# volume.net
KiCad netlist of a schematic drawn in EAGLE
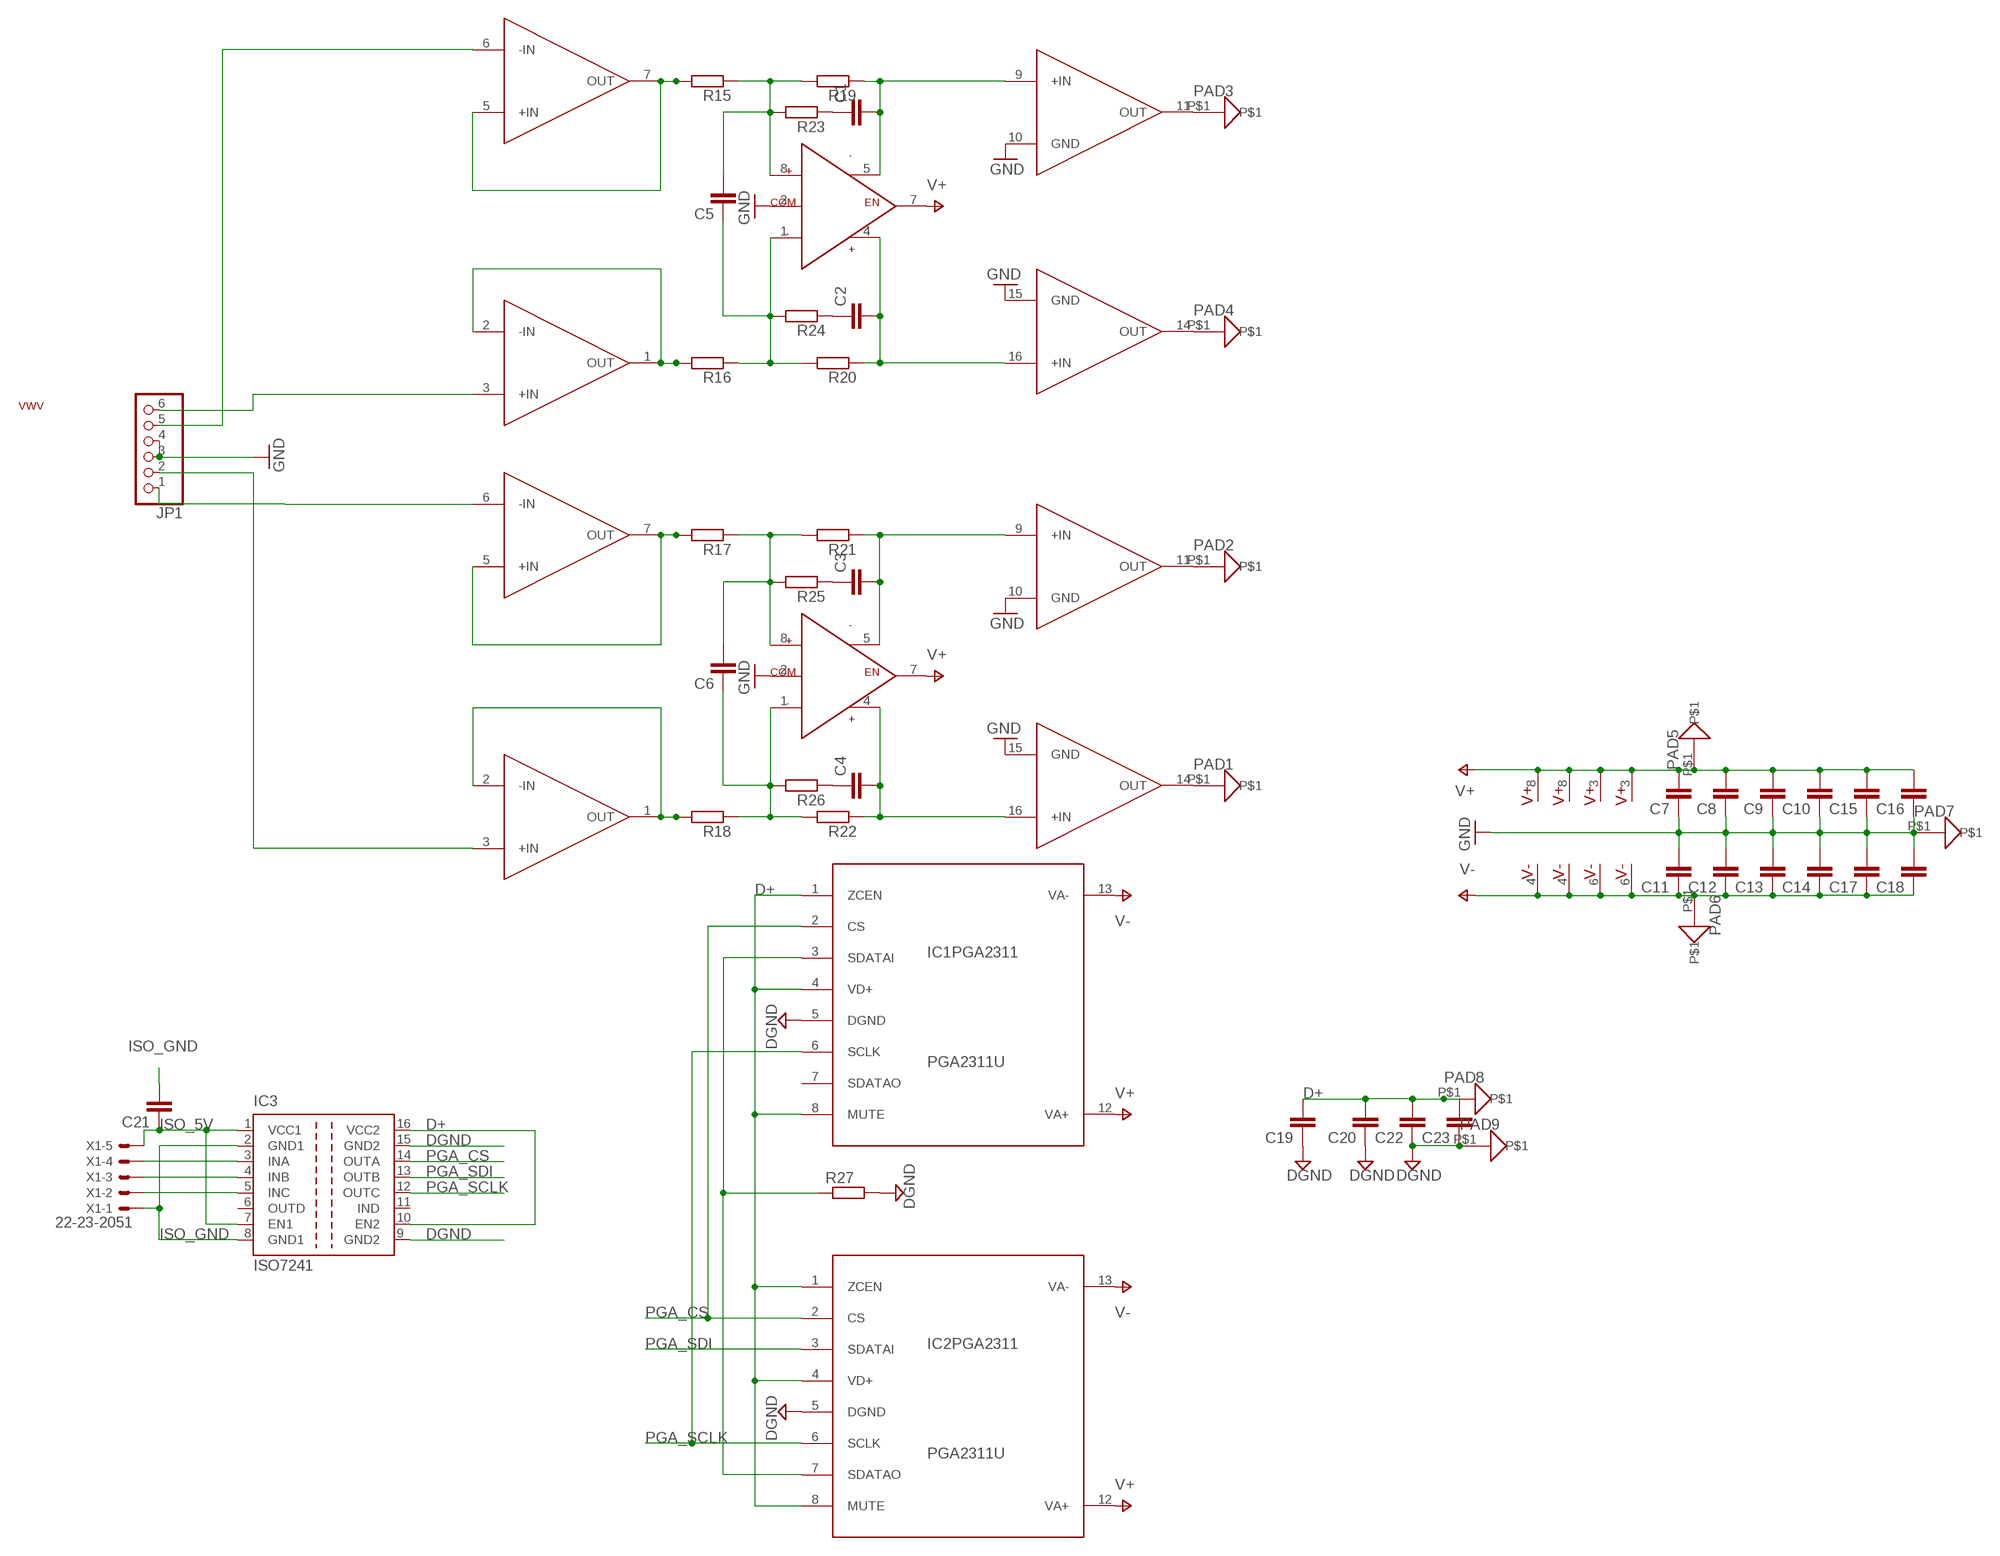
[diagram p0: schematic, sheet 1]

(export (version "E")
  (design (tool "Eeschema 10.0.6"))
  (components
    (comp (ref "C1")
      (value "C-EUC0805")
      (footprint "eagle-import:C0805")
      (libsource (lib "eagle-import") (part "C-EUC0805"))
    )
    (comp (ref "C2")
      (value "C-EUC0805")
      (footprint "eagle-import:C0805")
      (libsource (lib "eagle-import") (part "C-EUC0805"))
    )
    (comp (ref "C3")
      (value "C-EUC0805")
      (footprint "eagle-import:C0805")
      (libsource (lib "eagle-import") (part "C-EUC0805"))
    )
    (comp (ref "C4")
      (value "C-EUC0805")
      (footprint "eagle-import:C0805")
      (libsource (lib "eagle-import") (part "C-EUC0805"))
    )
    (comp (ref "C5")
      (value "C-EUC0805")
      (footprint "eagle-import:C0805")
      (libsource (lib "eagle-import") (part "C-EUC0805"))
    )
    (comp (ref "C6")
      (value "C-EUC0805")
      (footprint "eagle-import:C0805")
      (libsource (lib "eagle-import") (part "C-EUC0805"))
    )
    (comp (ref "C7")
      (value "C-EUC0805")
      (footprint "eagle-import:C0805")
      (libsource (lib "eagle-import") (part "C-EUC0805"))
    )
    (comp (ref "C8")
      (value "C-EUC0805")
      (footprint "eagle-import:C0805")
      (libsource (lib "eagle-import") (part "C-EUC0805"))
    )
    (comp (ref "C9")
      (value "C-EUC0805")
      (footprint "eagle-import:C0805")
      (libsource (lib "eagle-import") (part "C-EUC0805"))
    )
    (comp (ref "C10")
      (value "C-EUC0805")
      (footprint "eagle-import:C0805")
      (libsource (lib "eagle-import") (part "C-EUC0805"))
    )
    (comp (ref "C11")
      (value "C-EUC0805")
      (footprint "eagle-import:C0805")
      (libsource (lib "eagle-import") (part "C-EUC0805"))
    )
    (comp (ref "C12")
      (value "C-EUC0805")
      (footprint "eagle-import:C0805")
      (libsource (lib "eagle-import") (part "C-EUC0805"))
    )
    (comp (ref "C13")
      (value "C-EUC0805")
      (footprint "eagle-import:C0805")
      (libsource (lib "eagle-import") (part "C-EUC0805"))
    )
    (comp (ref "C14")
      (value "C-EUC0805")
      (footprint "eagle-import:C0805")
      (libsource (lib "eagle-import") (part "C-EUC0805"))
    )
    (comp (ref "C15")
      (value "C-EUC0805")
      (footprint "eagle-import:C0805")
      (libsource (lib "eagle-import") (part "C-EUC0805"))
    )
    (comp (ref "C16")
      (value "C-EUC0805")
      (footprint "eagle-import:C0805")
      (libsource (lib "eagle-import") (part "C-EUC0805"))
    )
    (comp (ref "C17")
      (value "C-EUC0805")
      (footprint "eagle-import:C0805")
      (libsource (lib "eagle-import") (part "C-EUC0805"))
    )
    (comp (ref "C18")
      (value "C-EUC0805")
      (footprint "eagle-import:C0805")
      (libsource (lib "eagle-import") (part "C-EUC0805"))
    )
    (comp (ref "C19")
      (value "C-EUC0805")
      (footprint "eagle-import:C0805")
      (libsource (lib "eagle-import") (part "C-EUC0805"))
    )
    (comp (ref "C20")
      (value "C-EUC0805")
      (footprint "eagle-import:C0805")
      (libsource (lib "eagle-import") (part "C-EUC0805"))
    )
    (comp (ref "C21")
      (value "C-EUC0805")
      (footprint "eagle-import:C0805")
      (libsource (lib "eagle-import") (part "C-EUC0805"))
    )
    (comp (ref "C22")
      (value "C-EUC0805")
      (footprint "eagle-import:C0805")
      (libsource (lib "eagle-import") (part "C-EUC0805"))
    )
    (comp (ref "C23")
      (value "C-EUC0805")
      (footprint "eagle-import:C0805")
      (libsource (lib "eagle-import") (part "C-EUC0805"))
    )
    (comp (ref "IC1")
      (value "PGA2311U")
      (footprint "eagle-import:SO16-1")
      (libsource (lib "eagle-import") (part "PGA2311U"))
    )
    (comp (ref "IC2")
      (value "PGA2311U")
      (footprint "eagle-import:SO16-1")
      (libsource (lib "eagle-import") (part "PGA2311U"))
    )
    (comp (ref "IC3")
      (value "ISO7241")
      (footprint "eagle-import:SO-16DW")
      (fields (field (name "MPN") "ISO7241CDW"))
      (libsource (lib "eagle-import") (part "ISO7241"))
    )
    (comp (ref "JP1")
      (value "PINHD-1X6")
      (footprint "eagle-import:1X06")
      (libsource (lib "eagle-import") (part "PINHD-1X6"))
    )
    (comp (ref "PAD1")
      (value "PAD8")
      (footprint "eagle-import:PAD-8")
      (libsource (lib "eagle-import") (part "PAD8"))
    )
    (comp (ref "PAD2")
      (value "PAD8")
      (footprint "eagle-import:PAD-8")
      (libsource (lib "eagle-import") (part "PAD8"))
    )
    (comp (ref "PAD3")
      (value "PAD8")
      (footprint "eagle-import:PAD-8")
      (libsource (lib "eagle-import") (part "PAD8"))
    )
    (comp (ref "PAD4")
      (value "PAD8")
      (footprint "eagle-import:PAD-8")
      (libsource (lib "eagle-import") (part "PAD8"))
    )
    (comp (ref "PAD5")
      (value "PAD8")
      (footprint "eagle-import:PAD-8")
      (libsource (lib "eagle-import") (part "PAD8"))
    )
    (comp (ref "PAD6")
      (value "PAD8")
      (footprint "eagle-import:PAD-8")
      (libsource (lib "eagle-import") (part "PAD8"))
    )
    (comp (ref "PAD7")
      (value "PAD8")
      (footprint "eagle-import:PAD-8")
      (libsource (lib "eagle-import") (part "PAD8"))
    )
    (comp (ref "PAD8")
      (value "PAD8")
      (footprint "eagle-import:PAD-8")
      (libsource (lib "eagle-import") (part "PAD8"))
    )
    (comp (ref "PAD9")
      (value "PAD8")
      (footprint "eagle-import:PAD-8")
      (libsource (lib "eagle-import") (part "PAD8"))
    )
    (comp (ref "R15")
      (value "R-EU_MELF0204W")
      (footprint "eagle-import:MINI_MELF-0204W")
      (libsource (lib "eagle-import") (part "R-EU_MELF0204W"))
    )
    (comp (ref "R16")
      (value "R-EU_MELF0204W")
      (footprint "eagle-import:MINI_MELF-0204W")
      (libsource (lib "eagle-import") (part "R-EU_MELF0204W"))
    )
    (comp (ref "R17")
      (value "R-EU_MELF0204W")
      (footprint "eagle-import:MINI_MELF-0204W")
      (libsource (lib "eagle-import") (part "R-EU_MELF0204W"))
    )
    (comp (ref "R18")
      (value "R-EU_MELF0204W")
      (footprint "eagle-import:MINI_MELF-0204W")
      (libsource (lib "eagle-import") (part "R-EU_MELF0204W"))
    )
    (comp (ref "R19")
      (value "R-EU_MELF0204W")
      (footprint "eagle-import:MINI_MELF-0204W")
      (libsource (lib "eagle-import") (part "R-EU_MELF0204W"))
    )
    (comp (ref "R20")
      (value "R-EU_MELF0204W")
      (footprint "eagle-import:MINI_MELF-0204W")
      (libsource (lib "eagle-import") (part "R-EU_MELF0204W"))
    )
    (comp (ref "R21")
      (value "R-EU_MELF0204W")
      (footprint "eagle-import:MINI_MELF-0204W")
      (libsource (lib "eagle-import") (part "R-EU_MELF0204W"))
    )
    (comp (ref "R22")
      (value "R-EU_MELF0204W")
      (footprint "eagle-import:MINI_MELF-0204W")
      (libsource (lib "eagle-import") (part "R-EU_MELF0204W"))
    )
    (comp (ref "R23")
      (value "R-EU_MELF0204W")
      (footprint "eagle-import:MINI_MELF-0204W")
      (libsource (lib "eagle-import") (part "R-EU_MELF0204W"))
    )
    (comp (ref "R24")
      (value "R-EU_MELF0204W")
      (footprint "eagle-import:MINI_MELF-0204W")
      (libsource (lib "eagle-import") (part "R-EU_MELF0204W"))
    )
    (comp (ref "R25")
      (value "R-EU_MELF0204W")
      (footprint "eagle-import:MINI_MELF-0204W")
      (libsource (lib "eagle-import") (part "R-EU_MELF0204W"))
    )
    (comp (ref "R26")
      (value "R-EU_MELF0204W")
      (footprint "eagle-import:MINI_MELF-0204W")
      (libsource (lib "eagle-import") (part "R-EU_MELF0204W"))
    )
    (comp (ref "R27")
      (value "R-EU_MELF0204W")
      (footprint "eagle-import:MINI_MELF-0204W")
      (libsource (lib "eagle-import") (part "R-EU_MELF0204W"))
    )
    (comp (ref "S1")
      (value "VWV")
      (footprint "eagle-import:VWV")
      (libsource (lib "eagle-import") (part "VWV"))
    )
    (comp (ref "U$1")
      (value "OPA1632")
      (footprint "eagle-import:SO8")
      (libsource (lib "eagle-import") (part "OPA1632"))
    )
    (comp (ref "U$2")
      (value "OPA1632")
      (footprint "eagle-import:SO8")
      (libsource (lib "eagle-import") (part "OPA1632"))
    )
    (comp (ref "U$3")
      (value "OP_DUALSOIC-8")
      (footprint "eagle-import:SOIC8")
      (libsource (lib "eagle-import") (part "OP_DUALSOIC-8"))
    )
    (comp (ref "U$4")
      (value "OP_DUALSOIC-8")
      (footprint "eagle-import:SOIC8")
      (libsource (lib "eagle-import") (part "OP_DUALSOIC-8"))
    )
    (comp (ref "X1")
      (value "22-23-2051")
      (footprint "eagle-import:22-23-2051")
      (fields (field (name "MF") "MOLEX"))
      (libsource (lib "eagle-import") (part "22-23-2051"))
    )
  )
  (nets
    (net (code "1") (name "/D+") (class "Default")
      (node (ref "C19") (pin "2") (pinfunction "2_2") (pintype "passive"))
      (node (ref "C20") (pin "2") (pinfunction "2_2") (pintype "passive"))
      (node (ref "C22") (pin "2") (pinfunction "2_2") (pintype "passive"))
      (node (ref "C23") (pin "2") (pinfunction "2_2") (pintype "passive"))
      (node (ref "IC1") (pin "1") (pinfunction "ZCEN_1") (pintype "input"))
      (node (ref "IC1") (pin "4") (pinfunction "VD+_4") (pintype "power_in"))
      (node (ref "IC1") (pin "8") (pinfunction "MUTE_8") (pintype "input"))
      (node (ref "IC2") (pin "1") (pinfunction "ZCEN_1") (pintype "input"))
      (node (ref "IC2") (pin "4") (pinfunction "VD+_4") (pintype "power_in"))
      (node (ref "IC2") (pin "8") (pinfunction "MUTE_8") (pintype "input"))
      (node (ref "IC3") (pin "10") (pinfunction "EN2_10") (pintype "input"))
      (node (ref "IC3") (pin "16") (pinfunction "VCC2_16") (pintype "power_in"))
      (node (ref "PAD8") (pin "P$1") (pinfunction "P$1_P$1") (pintype "bidirectional"))
    )
    (net (code "2") (name "/ISO_5V") (class "Default")
      (node (ref "C21") (pin "1") (pinfunction "1_1") (pintype "passive"))
      (node (ref "IC3") (pin "1") (pinfunction "VCC1_1") (pintype "power_in"))
      (node (ref "IC3") (pin "7") (pinfunction "EN1_7") (pintype "input"))
      (node (ref "X1") (pin "5") (pinfunction "S_5") (pintype "passive"))
    )
    (net (code "3") (name "/ISO_GND") (class "Default")
      (node (ref "C21") (pin "2") (pinfunction "2_2") (pintype "passive"))
      (node (ref "IC3") (pin "2") (pinfunction "GND1_2") (pintype "power_in"))
      (node (ref "IC3") (pin "8") (pinfunction "GND1_8") (pintype "power_in"))
      (node (ref "X1") (pin "1") (pinfunction "S_1") (pintype "passive"))
    )
    (net (code "4") (name "/PGA_CS") (class "Default")
      (node (ref "IC1") (pin "2") (pinfunction "CS_2") (pintype "bidirectional"))
      (node (ref "IC2") (pin "2") (pinfunction "CS_2") (pintype "bidirectional"))
      (node (ref "IC3") (pin "14") (pinfunction "OUTA_14") (pintype "output"))
    )
    (net (code "5") (name "/PGA_SCLK") (class "Default")
      (node (ref "IC1") (pin "6") (pinfunction "SCLK_6") (pintype "input"))
      (node (ref "IC2") (pin "6") (pinfunction "SCLK_6") (pintype "input"))
      (node (ref "IC3") (pin "12") (pinfunction "OUTC_12") (pintype "output"))
    )
    (net (code "6") (name "/PGA_SDI") (class "Default")
      (node (ref "IC2") (pin "3") (pinfunction "SDATAI_3") (pintype "input"))
      (node (ref "IC3") (pin "13") (pinfunction "OUTB_13") (pintype "output"))
    )
    (net (code "7") (name "DGND") (class "Default")
      (node (ref "C19") (pin "1") (pinfunction "1_1") (pintype "passive"))
      (node (ref "C20") (pin "1") (pinfunction "1_1") (pintype "passive"))
      (node (ref "C22") (pin "1") (pinfunction "1_1") (pintype "passive"))
      (node (ref "C23") (pin "1") (pinfunction "1_1") (pintype "passive"))
      (node (ref "IC1") (pin "5") (pinfunction "DGND_5") (pintype "power_in"))
      (node (ref "IC2") (pin "5") (pinfunction "DGND_5") (pintype "power_in"))
      (node (ref "IC3") (pin "15") (pinfunction "GND2_15") (pintype "power_in"))
      (node (ref "IC3") (pin "9") (pinfunction "GND2_9") (pintype "power_in"))
      (node (ref "PAD9") (pin "P$1") (pinfunction "P$1_P$1") (pintype "bidirectional"))
      (node (ref "R27") (pin "2") (pinfunction "2_2") (pintype "passive"))
    )
    (net (code "8") (name "GND") (class "Default")
      (node (ref "C10") (pin "1") (pinfunction "1_1") (pintype "passive"))
      (node (ref "C11") (pin "2") (pinfunction "2_2") (pintype "passive"))
      (node (ref "C12") (pin "2") (pinfunction "2_2") (pintype "passive"))
      (node (ref "C13") (pin "2") (pinfunction "2_2") (pintype "passive"))
      (node (ref "C14") (pin "2") (pinfunction "2_2") (pintype "passive"))
      (node (ref "C15") (pin "1") (pinfunction "1_1") (pintype "passive"))
      (node (ref "C16") (pin "1") (pinfunction "1_1") (pintype "passive"))
      (node (ref "C17") (pin "2") (pinfunction "2_2") (pintype "passive"))
      (node (ref "C18") (pin "2") (pinfunction "2_2") (pintype "passive"))
      (node (ref "C7") (pin "1") (pinfunction "1_1") (pintype "passive"))
      (node (ref "C8") (pin "1") (pinfunction "1_1") (pintype "passive"))
      (node (ref "C9") (pin "1") (pinfunction "1_1") (pintype "passive"))
      (node (ref "IC1") (pin "10") (pinfunction "GND_10") (pintype "bidirectional"))
      (node (ref "IC1") (pin "15") (pinfunction "GND_15") (pintype "bidirectional"))
      (node (ref "IC2") (pin "10") (pinfunction "GND_10") (pintype "bidirectional"))
      (node (ref "IC2") (pin "15") (pinfunction "GND_15") (pintype "bidirectional"))
      (node (ref "JP1") (pin "3") (pinfunction "3_3") (pintype "passive"))
      (node (ref "JP1") (pin "4") (pinfunction "4_4") (pintype "passive"))
      (node (ref "PAD7") (pin "P$1") (pinfunction "P$1_P$1") (pintype "bidirectional"))
      (node (ref "U$1") (pin "2") (pinfunction "COM_2") (pintype "bidirectional"))
      (node (ref "U$2") (pin "2") (pinfunction "COM_2") (pintype "bidirectional"))
    )
    (net (code "9") (name "Net-(C1-Pad1)") (class "Default")
      (node (ref "C1") (pin "1") (pinfunction "1_1") (pintype "passive"))
      (node (ref "R23") (pin "1") (pinfunction "1_1") (pintype "passive"))
    )
    (net (code "10") (name "Net-(C2-Pad1)") (class "Default")
      (node (ref "C2") (pin "1") (pinfunction "1_1") (pintype "passive"))
      (node (ref "R24") (pin "1") (pinfunction "1_1") (pintype "passive"))
    )
    (net (code "11") (name "Net-(C3-Pad1)") (class "Default")
      (node (ref "C3") (pin "1") (pinfunction "1_1") (pintype "passive"))
      (node (ref "R25") (pin "1") (pinfunction "1_1") (pintype "passive"))
    )
    (net (code "12") (name "Net-(C4-Pad1)") (class "Default")
      (node (ref "C4") (pin "1") (pinfunction "1_1") (pintype "passive"))
      (node (ref "R26") (pin "1") (pinfunction "1_1") (pintype "passive"))
    )
    (net (code "13") (name "Net-(IC1A-+IN)") (class "Default")
      (node (ref "C1") (pin "2") (pinfunction "2_2") (pintype "passive"))
      (node (ref "IC1") (pin "9") (pinfunction "+IN_9") (pintype "bidirectional"))
      (node (ref "R19") (pin "1") (pinfunction "1_1") (pintype "passive"))
      (node (ref "U$1") (pin "5") (pinfunction "OUT-_5") (pintype "bidirectional"))
    )
    (net (code "14") (name "Net-(IC1A-OUT)") (class "Default")
      (node (ref "IC1") (pin "11") (pinfunction "OUT_11") (pintype "bidirectional"))
      (node (ref "PAD3") (pin "P$1") (pinfunction "P$1_P$1") (pintype "bidirectional"))
    )
    (net (code "15") (name "Net-(IC1B-+IN)") (class "Default")
      (node (ref "C2") (pin "2") (pinfunction "2_2") (pintype "passive"))
      (node (ref "IC1") (pin "16") (pinfunction "+IN_16") (pintype "bidirectional"))
      (node (ref "R20") (pin "1") (pinfunction "1_1") (pintype "passive"))
      (node (ref "U$1") (pin "4") (pinfunction "OUT+_4") (pintype "bidirectional"))
    )
    (net (code "16") (name "Net-(IC1B-OUT)") (class "Default")
      (node (ref "IC1") (pin "14") (pinfunction "OUT_14") (pintype "bidirectional"))
      (node (ref "PAD4") (pin "P$1") (pinfunction "P$1_P$1") (pintype "bidirectional"))
    )
    (net (code "17") (name "Net-(IC1C-SDATAI)") (class "Default")
      (node (ref "IC1") (pin "3") (pinfunction "SDATAI_3") (pintype "input"))
      (node (ref "IC2") (pin "7") (pinfunction "SDATAO_7") (pintype "output"))
      (node (ref "R27") (pin "1") (pinfunction "1_1") (pintype "passive"))
    )
    (net (code "18") (name "Net-(IC2A-+IN)") (class "Default")
      (node (ref "C3") (pin "2") (pinfunction "2_2") (pintype "passive"))
      (node (ref "IC2") (pin "9") (pinfunction "+IN_9") (pintype "bidirectional"))
      (node (ref "R21") (pin "1") (pinfunction "1_1") (pintype "passive"))
      (node (ref "U$2") (pin "5") (pinfunction "OUT-_5") (pintype "bidirectional"))
    )
    (net (code "19") (name "Net-(IC2A-OUT)") (class "Default")
      (node (ref "IC2") (pin "11") (pinfunction "OUT_11") (pintype "bidirectional"))
      (node (ref "PAD2") (pin "P$1") (pinfunction "P$1_P$1") (pintype "bidirectional"))
    )
    (net (code "20") (name "Net-(IC2B-+IN)") (class "Default")
      (node (ref "C4") (pin "2") (pinfunction "2_2") (pintype "passive"))
      (node (ref "IC2") (pin "16") (pinfunction "+IN_16") (pintype "bidirectional"))
      (node (ref "R22") (pin "1") (pinfunction "1_1") (pintype "passive"))
      (node (ref "U$2") (pin "4") (pinfunction "OUT+_4") (pintype "bidirectional"))
    )
    (net (code "21") (name "Net-(IC2B-OUT)") (class "Default")
      (node (ref "IC2") (pin "14") (pinfunction "OUT_14") (pintype "bidirectional"))
      (node (ref "PAD1") (pin "P$1") (pinfunction "P$1_P$1") (pintype "bidirectional"))
    )
    (net (code "22") (name "Net-(IC3-INA)") (class "Default")
      (node (ref "IC3") (pin "3") (pinfunction "INA_3") (pintype "input"))
      (node (ref "X1") (pin "4") (pinfunction "S_4") (pintype "passive"))
    )
    (net (code "23") (name "Net-(IC3-INB)") (class "Default")
      (node (ref "IC3") (pin "4") (pinfunction "INB_4") (pintype "input"))
      (node (ref "X1") (pin "3") (pinfunction "S_3") (pintype "passive"))
    )
    (net (code "24") (name "Net-(IC3-INC)") (class "Default")
      (node (ref "IC3") (pin "5") (pinfunction "INC_5") (pintype "input"))
      (node (ref "X1") (pin "2") (pinfunction "S_2") (pintype "passive"))
    )
    (net (code "25") (name "Net-(U$1A-IN+)") (class "Default")
      (node (ref "C5") (pin "2") (pinfunction "2_2") (pintype "passive"))
      (node (ref "R15") (pin "1") (pinfunction "1_1") (pintype "passive"))
      (node (ref "R19") (pin "2") (pinfunction "2_2") (pintype "passive"))
      (node (ref "R23") (pin "2") (pinfunction "2_2") (pintype "passive"))
      (node (ref "U$1") (pin "8") (pinfunction "IN+_8") (pintype "bidirectional"))
    )
    (net (code "26") (name "Net-(U$1A-IN-)") (class "Default")
      (node (ref "C5") (pin "1") (pinfunction "1_1") (pintype "passive"))
      (node (ref "R16") (pin "1") (pinfunction "1_1") (pintype "passive"))
      (node (ref "R20") (pin "2") (pinfunction "2_2") (pintype "passive"))
      (node (ref "R24") (pin "2") (pinfunction "2_2") (pintype "passive"))
      (node (ref "U$1") (pin "1") (pinfunction "IN-_1") (pintype "bidirectional"))
    )
    (net (code "27") (name "Net-(U$2A-IN+)") (class "Default")
      (node (ref "C6") (pin "2") (pinfunction "2_2") (pintype "passive"))
      (node (ref "R17") (pin "1") (pinfunction "1_1") (pintype "passive"))
      (node (ref "R21") (pin "2") (pinfunction "2_2") (pintype "passive"))
      (node (ref "R25") (pin "2") (pinfunction "2_2") (pintype "passive"))
      (node (ref "U$2") (pin "8") (pinfunction "IN+_8") (pintype "bidirectional"))
    )
    (net (code "28") (name "Net-(U$2A-IN-)") (class "Default")
      (node (ref "C6") (pin "1") (pinfunction "1_1") (pintype "passive"))
      (node (ref "R18") (pin "1") (pinfunction "1_1") (pintype "passive"))
      (node (ref "R22") (pin "2") (pinfunction "2_2") (pintype "passive"))
      (node (ref "R26") (pin "2") (pinfunction "2_2") (pintype "passive"))
      (node (ref "U$2") (pin "1") (pinfunction "IN-_1") (pintype "bidirectional"))
    )
    (net (code "29") (name "Net-(U$3A-+IN)") (class "Default")
      (node (ref "JP1") (pin "6") (pinfunction "6_6") (pintype "passive"))
      (node (ref "U$3") (pin "3") (pinfunction "+IN_3") (pintype "bidirectional"))
    )
    (net (code "30") (name "Net-(U$3A--IN)") (class "Default")
      (node (ref "R16") (pin "2") (pinfunction "2_2") (pintype "passive"))
      (node (ref "U$3") (pin "1") (pinfunction "OUT_1") (pintype "bidirectional"))
      (node (ref "U$3") (pin "2") (pinfunction "-IN_2") (pintype "bidirectional"))
    )
    (net (code "31") (name "Net-(U$3B-+IN)") (class "Default")
      (node (ref "R15") (pin "2") (pinfunction "2_2") (pintype "passive"))
      (node (ref "U$3") (pin "5") (pinfunction "+IN_5") (pintype "bidirectional"))
      (node (ref "U$3") (pin "7") (pinfunction "OUT_7") (pintype "bidirectional"))
    )
    (net (code "32") (name "Net-(U$3B--IN)") (class "Default")
      (node (ref "JP1") (pin "5") (pinfunction "5_5") (pintype "passive"))
      (node (ref "U$3") (pin "6") (pinfunction "-IN_6") (pintype "bidirectional"))
    )
    (net (code "33") (name "Net-(U$4A-+IN)") (class "Default")
      (node (ref "JP1") (pin "2") (pinfunction "2_2") (pintype "passive"))
      (node (ref "U$4") (pin "3") (pinfunction "+IN_3") (pintype "bidirectional"))
    )
    (net (code "34") (name "Net-(U$4A--IN)") (class "Default")
      (node (ref "R18") (pin "2") (pinfunction "2_2") (pintype "passive"))
      (node (ref "U$4") (pin "1") (pinfunction "OUT_1") (pintype "bidirectional"))
      (node (ref "U$4") (pin "2") (pinfunction "-IN_2") (pintype "bidirectional"))
    )
    (net (code "35") (name "Net-(U$4B-+IN)") (class "Default")
      (node (ref "R17") (pin "2") (pinfunction "2_2") (pintype "passive"))
      (node (ref "U$4") (pin "5") (pinfunction "+IN_5") (pintype "bidirectional"))
      (node (ref "U$4") (pin "7") (pinfunction "OUT_7") (pintype "bidirectional"))
    )
    (net (code "36") (name "Net-(U$4B--IN)") (class "Default")
      (node (ref "JP1") (pin "1") (pinfunction "1_1") (pintype "passive"))
      (node (ref "U$4") (pin "6") (pinfunction "-IN_6") (pintype "bidirectional"))
    )
    (net (code "37") (name "V+") (class "Default")
      (node (ref "C10") (pin "2") (pinfunction "2_2") (pintype "passive"))
      (node (ref "C15") (pin "2") (pinfunction "2_2") (pintype "passive"))
      (node (ref "C16") (pin "2") (pinfunction "2_2") (pintype "passive"))
      (node (ref "C7") (pin "2") (pinfunction "2_2") (pintype "passive"))
      (node (ref "C8") (pin "2") (pinfunction "2_2") (pintype "passive"))
      (node (ref "C9") (pin "2") (pinfunction "2_2") (pintype "passive"))
      (node (ref "IC1") (pin "12") (pinfunction "VA+_12") (pintype "power_in"))
      (node (ref "IC2") (pin "12") (pinfunction "VA+_12") (pintype "power_in"))
      (node (ref "PAD5") (pin "P$1") (pinfunction "P$1_P$1") (pintype "bidirectional"))
      (node (ref "U$1") (pin "3") (pinfunction "V+_3") (pintype "bidirectional"))
      (node (ref "U$1") (pin "7") (pinfunction "EN_7") (pintype "bidirectional"))
      (node (ref "U$2") (pin "3") (pinfunction "V+_3") (pintype "bidirectional"))
      (node (ref "U$2") (pin "7") (pinfunction "EN_7") (pintype "bidirectional"))
      (node (ref "U$3") (pin "8") (pinfunction "V+_8") (pintype "bidirectional"))
      (node (ref "U$4") (pin "8") (pinfunction "V+_8") (pintype "bidirectional"))
    )
    (net (code "38") (name "V-") (class "Default")
      (node (ref "C11") (pin "1") (pinfunction "1_1") (pintype "passive"))
      (node (ref "C12") (pin "1") (pinfunction "1_1") (pintype "passive"))
      (node (ref "C13") (pin "1") (pinfunction "1_1") (pintype "passive"))
      (node (ref "C14") (pin "1") (pinfunction "1_1") (pintype "passive"))
      (node (ref "C17") (pin "1") (pinfunction "1_1") (pintype "passive"))
      (node (ref "C18") (pin "1") (pinfunction "1_1") (pintype "passive"))
      (node (ref "IC1") (pin "13") (pinfunction "VA-_13") (pintype "power_in"))
      (node (ref "IC2") (pin "13") (pinfunction "VA-_13") (pintype "power_in"))
      (node (ref "PAD6") (pin "P$1") (pinfunction "P$1_P$1") (pintype "bidirectional"))
      (node (ref "U$1") (pin "6") (pinfunction "V-_6") (pintype "bidirectional"))
      (node (ref "U$2") (pin "6") (pinfunction "V-_6") (pintype "bidirectional"))
      (node (ref "U$3") (pin "4") (pinfunction "V-_4") (pintype "bidirectional"))
      (node (ref "U$4") (pin "4") (pinfunction "V-_4") (pintype "bidirectional"))
    )
    (net (code "39") (name "unconnected-(IC1C-SDATAO-Pad7)") (class "Default")
      (node (ref "IC1") (pin "7") (pinfunction "SDATAO_7") (pintype "output"))
    )
    (net (code "40") (name "unconnected-(IC3-IND-Pad11)") (class "Default")
      (node (ref "IC3") (pin "11") (pinfunction "IND_11") (pintype "input"))
    )
    (net (code "41") (name "unconnected-(IC3-OUTD-Pad6)") (class "Default")
      (node (ref "IC3") (pin "6") (pinfunction "OUTD_6") (pintype "output"))
    )
  )
)
